# 1541-3mf.net
KiCad netlist of a schematic drawn in EAGLE
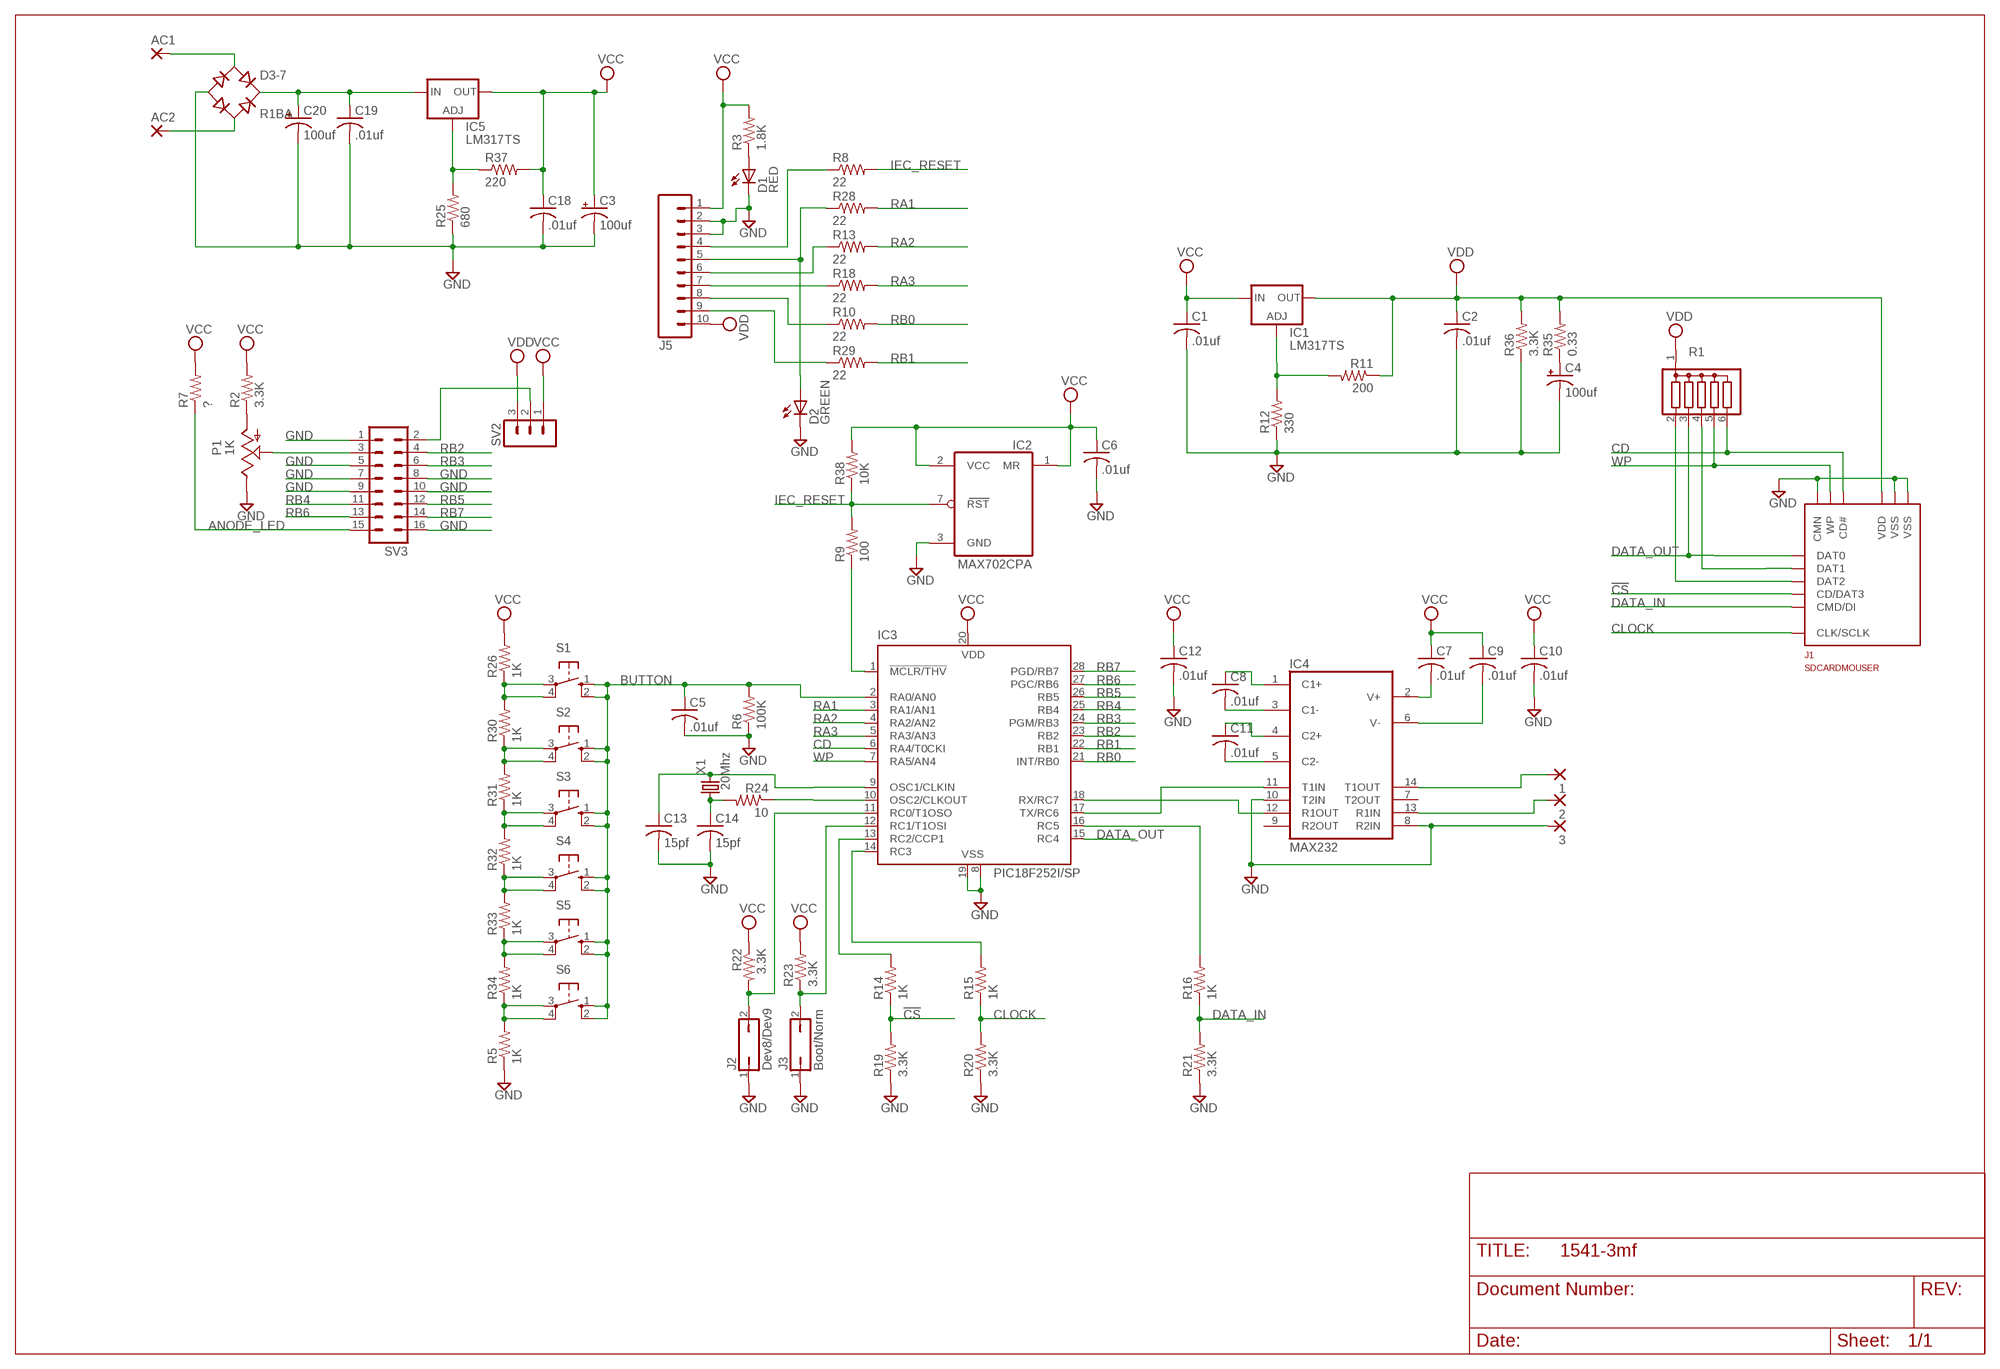
[diagram p0: schematic, sheet 1]

(export (version "E")
  (design (tool "Eeschema 10.0.6"))
  (components
    (comp (ref "1")
      (value "2,15/1,0")
      (footprint "eagle-import:2,15_1,0")
      (libsource (lib "eagle-import") (part "2,15/1,0"))
    )
    (comp (ref "2")
      (value "2,15/1,0")
      (footprint "eagle-import:2,15_1,0")
      (libsource (lib "eagle-import") (part "2,15/1,0"))
    )
    (comp (ref "3")
      (value "2,15/1,0")
      (footprint "eagle-import:2,15_1,0")
      (libsource (lib "eagle-import") (part "2,15/1,0"))
    )
    (comp (ref "AC1")
      (value "2,15/1,0")
      (footprint "eagle-import:2,15_1,0")
      (libsource (lib "eagle-import") (part "2,15/1,0"))
    )
    (comp (ref "AC2")
      (value "2,15/1,0")
      (footprint "eagle-import:2,15_1,0")
      (libsource (lib "eagle-import") (part "2,15/1,0"))
    )
    (comp (ref "C1")
      (value ".01uf")
      (footprint "eagle-import:C025-024X044")
      (libsource (lib "eagle-import") (part "C-US025-024X044"))
    )
    (comp (ref "C2")
      (value ".01uf")
      (footprint "eagle-import:C025-024X044")
      (libsource (lib "eagle-import") (part "C-US025-024X044"))
    )
    (comp (ref "C3")
      (value "100uf")
      (footprint "eagle-import:E2-5")
      (libsource (lib "eagle-import") (part "CPOL-USE2-5"))
    )
    (comp (ref "C4")
      (value "100uf")
      (footprint "eagle-import:E2-5")
      (libsource (lib "eagle-import") (part "CPOL-USE2-5"))
    )
    (comp (ref "C5")
      (value ".01uf")
      (footprint "eagle-import:C025-024X044")
      (libsource (lib "eagle-import") (part "C-US025-024X044"))
    )
    (comp (ref "C6")
      (value ".01uf")
      (footprint "eagle-import:C025-024X044")
      (libsource (lib "eagle-import") (part "C-US025-024X044"))
    )
    (comp (ref "C7")
      (value ".01uf")
      (footprint "eagle-import:C025-024X044")
      (libsource (lib "eagle-import") (part "C-US025-024X044"))
    )
    (comp (ref "C8")
      (value ".01uf")
      (footprint "eagle-import:C025-024X044")
      (libsource (lib "eagle-import") (part "C-US025-024X044"))
    )
    (comp (ref "C9")
      (value ".01uf")
      (footprint "eagle-import:C025-024X044")
      (libsource (lib "eagle-import") (part "C-US025-024X044"))
    )
    (comp (ref "C10")
      (value ".01uf")
      (footprint "eagle-import:C025-024X044")
      (libsource (lib "eagle-import") (part "C-US025-024X044"))
    )
    (comp (ref "C11")
      (value ".01uf")
      (footprint "eagle-import:C025-024X044")
      (libsource (lib "eagle-import") (part "C-US025-024X044"))
    )
    (comp (ref "C12")
      (value ".01uf")
      (footprint "eagle-import:C025-024X044")
      (libsource (lib "eagle-import") (part "C-US025-024X044"))
    )
    (comp (ref "C13")
      (value "15pf")
      (footprint "eagle-import:C025-024X044")
      (libsource (lib "eagle-import") (part "C-US025-024X044"))
    )
    (comp (ref "C14")
      (value "15pf")
      (footprint "eagle-import:C025-024X044")
      (libsource (lib "eagle-import") (part "C-US025-024X044"))
    )
    (comp (ref "C18")
      (value ".01uf")
      (footprint "eagle-import:C025-024X044")
      (libsource (lib "eagle-import") (part "C-US025-024X044"))
    )
    (comp (ref "C19")
      (value ".01uf")
      (footprint "eagle-import:C025-024X044")
      (libsource (lib "eagle-import") (part "C-US025-024X044"))
    )
    (comp (ref "C20")
      (value "100uf")
      (footprint "eagle-import:E2-5")
      (libsource (lib "eagle-import") (part "CPOL-USE2-5"))
    )
    (comp (ref "D1")
      (value "RED")
      (footprint "eagle-import:LED3MM")
      (libsource (lib "eagle-import") (part "LED3MM"))
    )
    (comp (ref "D2")
      (value "GREEN")
      (footprint "eagle-import:LED3MM")
      (libsource (lib "eagle-import") (part "LED3MM"))
    )
    (comp (ref "D3-7")
      (value "R1BA")
      (footprint "eagle-import:RB1A")
      (libsource (lib "eagle-import") (part "RB1A"))
    )
    (comp (ref "IC1")
      (value "LM317TS")
      (footprint "eagle-import:317TS")
      (libsource (lib "eagle-import") (part "LM317TS"))
    )
    (comp (ref "IC2")
      (value "MAX702CPA")
      (footprint "eagle-import:DIL08")
      (fields (field (name "MF") "MAXIM") (field (name "MPN") "MAX702CPA+"))
      (libsource (lib "eagle-import") (part "MAX702CPA"))
    )
    (comp (ref "IC3")
      (value "PIC18F252I/SP")
      (footprint "eagle-import:DIL28-3")
      (fields (field (name "MF") "MICROCHIP") (field (name "MPN") "PIC16F870-I/SP"))
      (libsource (lib "eagle-import") (part "PIC16870PF"))
    )
    (comp (ref "IC4")
      (value "MAX232")
      (footprint "eagle-import:DIL16")
      (fields (field (name "MF") "MAXIM") (field (name "MPN") "MAX232ACPE+"))
      (libsource (lib "eagle-import") (part "MAX232"))
    )
    (comp (ref "IC5")
      (value "LM317TS")
      (footprint "eagle-import:317TS")
      (libsource (lib "eagle-import") (part "LM317TS"))
    )
    (comp (ref "J1")
      (value "SDCARDMOUSER")
      (footprint "eagle-import:SCDA1A")
      (libsource (lib "eagle-import") (part "SDCARDMOUSER"))
    )
    (comp (ref "J2")
      (value "Dev8/Dev9")
      (footprint "eagle-import:JP1")
      (libsource (lib "eagle-import") (part "JP1Q"))
    )
    (comp (ref "J3")
      (value "Boot/Norm")
      (footprint "eagle-import:JP1")
      (libsource (lib "eagle-import") (part "JP1Q"))
    )
    (comp (ref "J5")
      (value "M10")
      (footprint "eagle-import:10P")
      (libsource (lib "eagle-import") (part "M10"))
    )
    (comp (ref "P1")
      (value "1K")
      (footprint "eagle-import:LI10")
      (libsource (lib "eagle-import") (part "TRIM_US-LI10"))
    )
    (comp (ref "R1")
      (value "G05R")
      (footprint "eagle-import:SIL6")
      (libsource (lib "eagle-import") (part "G05R"))
    )
    (comp (ref "R2")
      (value "3.3K")
      (footprint "eagle-import:0207_7")
      (libsource (lib "eagle-import") (part "R-US_0207/7"))
    )
    (comp (ref "R3")
      (value "1.8K")
      (footprint "eagle-import:0207_7")
      (libsource (lib "eagle-import") (part "R-US_0207/7"))
    )
    (comp (ref "R5")
      (value "1K")
      (footprint "eagle-import:0207_7")
      (libsource (lib "eagle-import") (part "R-US_0207/7"))
    )
    (comp (ref "R6")
      (value "100K")
      (footprint "eagle-import:0207_7")
      (libsource (lib "eagle-import") (part "R-US_0207/7"))
    )
    (comp (ref "R7")
      (value "?")
      (footprint "eagle-import:0207_7")
      (libsource (lib "eagle-import") (part "R-US_0207/7"))
    )
    (comp (ref "R8")
      (value "22")
      (footprint "eagle-import:0207_7")
      (libsource (lib "eagle-import") (part "R-US_0207/7"))
    )
    (comp (ref "R9")
      (value "100")
      (footprint "eagle-import:0207_7")
      (libsource (lib "eagle-import") (part "R-US_0207/7"))
    )
    (comp (ref "R10")
      (value "22")
      (footprint "eagle-import:0207_7")
      (libsource (lib "eagle-import") (part "R-US_0207/7"))
    )
    (comp (ref "R11")
      (value "200")
      (footprint "eagle-import:0207_7")
      (libsource (lib "eagle-import") (part "R-US_0207/7"))
    )
    (comp (ref "R12")
      (value "330")
      (footprint "eagle-import:0207_7")
      (libsource (lib "eagle-import") (part "R-US_0207/7"))
    )
    (comp (ref "R13")
      (value "22")
      (footprint "eagle-import:0207_7")
      (libsource (lib "eagle-import") (part "R-US_0207/7"))
    )
    (comp (ref "R14")
      (value "1K")
      (footprint "eagle-import:0207_7")
      (libsource (lib "eagle-import") (part "R-US_0207/7"))
    )
    (comp (ref "R15")
      (value "1K")
      (footprint "eagle-import:0207_7")
      (libsource (lib "eagle-import") (part "R-US_0207/7"))
    )
    (comp (ref "R16")
      (value "1K")
      (footprint "eagle-import:0207_7")
      (libsource (lib "eagle-import") (part "R-US_0207/7"))
    )
    (comp (ref "R18")
      (value "22")
      (footprint "eagle-import:0207_7")
      (libsource (lib "eagle-import") (part "R-US_0207/7"))
    )
    (comp (ref "R19")
      (value "3.3K")
      (footprint "eagle-import:0207_7")
      (libsource (lib "eagle-import") (part "R-US_0207/7"))
    )
    (comp (ref "R20")
      (value "3.3K")
      (footprint "eagle-import:0207_7")
      (libsource (lib "eagle-import") (part "R-US_0207/7"))
    )
    (comp (ref "R21")
      (value "3.3K")
      (footprint "eagle-import:0207_7")
      (libsource (lib "eagle-import") (part "R-US_0207/7"))
    )
    (comp (ref "R22")
      (value "3.3K")
      (footprint "eagle-import:0207_7")
      (libsource (lib "eagle-import") (part "R-US_0207/7"))
    )
    (comp (ref "R23")
      (value "3.3K")
      (footprint "eagle-import:0207_7")
      (libsource (lib "eagle-import") (part "R-US_0207/7"))
    )
    (comp (ref "R24")
      (value "10")
      (footprint "eagle-import:0207_7")
      (libsource (lib "eagle-import") (part "R-US_0207/7"))
    )
    (comp (ref "R25")
      (value "680")
      (footprint "eagle-import:0207_7")
      (libsource (lib "eagle-import") (part "R-US_0207/7"))
    )
    (comp (ref "R26")
      (value "1K")
      (footprint "eagle-import:0207_7")
      (libsource (lib "eagle-import") (part "R-US_0207/7"))
    )
    (comp (ref "R28")
      (value "22")
      (footprint "eagle-import:0207_7")
      (libsource (lib "eagle-import") (part "R-US_0207/7"))
    )
    (comp (ref "R29")
      (value "22")
      (footprint "eagle-import:0207_7")
      (libsource (lib "eagle-import") (part "R-US_0207/7"))
    )
    (comp (ref "R30")
      (value "1K")
      (footprint "eagle-import:0207_7")
      (libsource (lib "eagle-import") (part "R-US_0207/7"))
    )
    (comp (ref "R31")
      (value "1K")
      (footprint "eagle-import:0207_7")
      (libsource (lib "eagle-import") (part "R-US_0207/7"))
    )
    (comp (ref "R32")
      (value "1K")
      (footprint "eagle-import:0207_7")
      (libsource (lib "eagle-import") (part "R-US_0207/7"))
    )
    (comp (ref "R33")
      (value "1K")
      (footprint "eagle-import:0207_7")
      (libsource (lib "eagle-import") (part "R-US_0207/7"))
    )
    (comp (ref "R34")
      (value "1K")
      (footprint "eagle-import:0207_7")
      (libsource (lib "eagle-import") (part "R-US_0207/7"))
    )
    (comp (ref "R35")
      (value "0.33")
      (footprint "eagle-import:0207_7")
      (libsource (lib "eagle-import") (part "R-US_0207/7"))
    )
    (comp (ref "R36")
      (value "3.3K")
      (footprint "eagle-import:0207_7")
      (libsource (lib "eagle-import") (part "R-US_0207/7"))
    )
    (comp (ref "R37")
      (value "220")
      (footprint "eagle-import:0207_7")
      (libsource (lib "eagle-import") (part "R-US_0207/7"))
    )
    (comp (ref "R38")
      (value "10K")
      (footprint "eagle-import:0207_7")
      (libsource (lib "eagle-import") (part "R-US_0207/7"))
    )
    (comp (ref "S1")
      (value "10-XX")
      (footprint "eagle-import:B3F-10XX")
      (fields (field (name "MPN") "B3F-1000"))
      (libsource (lib "eagle-import") (part "10-XX"))
    )
    (comp (ref "S2")
      (value "10-XX")
      (footprint "eagle-import:B3F-10XX")
      (fields (field (name "MPN") "B3F-1000"))
      (libsource (lib "eagle-import") (part "10-XX"))
    )
    (comp (ref "S3")
      (value "10-XX")
      (footprint "eagle-import:B3F-10XX")
      (fields (field (name "MPN") "B3F-1000"))
      (libsource (lib "eagle-import") (part "10-XX"))
    )
    (comp (ref "S4")
      (value "10-XX")
      (footprint "eagle-import:B3F-10XX")
      (fields (field (name "MPN") "B3F-1000"))
      (libsource (lib "eagle-import") (part "10-XX"))
    )
    (comp (ref "S5")
      (value "10-XX")
      (footprint "eagle-import:B3F-10XX")
      (fields (field (name "MPN") "B3F-1000"))
      (libsource (lib "eagle-import") (part "10-XX"))
    )
    (comp (ref "S6")
      (value "10-XX")
      (footprint "eagle-import:B3F-10XX")
      (fields (field (name "MPN") "B3F-1000"))
      (libsource (lib "eagle-import") (part "10-XX"))
    )
    (comp (ref "SV2")
      (value "MA03-1")
      (footprint "eagle-import:MA03-1")
      (libsource (lib "eagle-import") (part "MA03-1"))
    )
    (comp (ref "SV3")
      (value "ML16")
      (footprint "eagle-import:ML16")
      (libsource (lib "eagle-import") (part "ML16"))
    )
    (comp (ref "X1")
      (value "20Mhz")
      (footprint "eagle-import:HC49U70")
      (libsource (lib "eagle-import") (part "CRYSTALHC49U70"))
    )
  )
  (nets
    (net (code "1") (name "/ANODE_LED") (class "Default")
      (node (ref "R7") (pin "1") (pinfunction "1_1") (pintype "passive"))
      (node (ref "SV3") (pin "15") (pinfunction "15_15") (pintype "passive"))
    )
    (net (code "2") (name "/BUTTON") (class "Default")
      (node (ref "C5") (pin "1") (pinfunction "1_1") (pintype "passive"))
      (node (ref "IC3") (pin "2") (pinfunction "RA0/AN0_2") (pintype "bidirectional"))
      (node (ref "R6") (pin "2") (pinfunction "2_2") (pintype "passive"))
      (node (ref "S1") (pin "1") (pinfunction "S_1") (pintype "passive"))
      (node (ref "S1") (pin "2") (pinfunction "S1_2") (pintype "passive"))
      (node (ref "S2") (pin "1") (pinfunction "S_1") (pintype "passive"))
      (node (ref "S2") (pin "2") (pinfunction "S1_2") (pintype "passive"))
      (node (ref "S3") (pin "1") (pinfunction "S_1") (pintype "passive"))
      (node (ref "S3") (pin "2") (pinfunction "S1_2") (pintype "passive"))
      (node (ref "S4") (pin "1") (pinfunction "S_1") (pintype "passive"))
      (node (ref "S4") (pin "2") (pinfunction "S1_2") (pintype "passive"))
      (node (ref "S5") (pin "1") (pinfunction "S_1") (pintype "passive"))
      (node (ref "S5") (pin "2") (pinfunction "S1_2") (pintype "passive"))
      (node (ref "S6") (pin "1") (pinfunction "S_1") (pintype "passive"))
      (node (ref "S6") (pin "2") (pinfunction "S1_2") (pintype "passive"))
    )
    (net (code "3") (name "/CD") (class "Default")
      (node (ref "IC3") (pin "6") (pinfunction "RA4/T0CKI_6") (pintype "bidirectional"))
      (node (ref "J1") (pin "10") (pinfunction "CD#_10") (pintype "output"))
      (node (ref "R1") (pin "6") (pinfunction "6_6") (pintype "passive"))
    )
    (net (code "4") (name "/CLOCK") (class "Default")
      (node (ref "J1") (pin "5") (pinfunction "CLK/SCLK_5") (pintype "bidirectional"))
      (node (ref "R15") (pin "1") (pinfunction "1_1") (pintype "passive"))
      (node (ref "R20") (pin "2") (pinfunction "2_2") (pintype "passive"))
    )
    (net (code "5") (name "/DATA_IN") (class "Default")
      (node (ref "J1") (pin "2") (pinfunction "CMD/DI_2") (pintype "bidirectional"))
      (node (ref "R16") (pin "1") (pinfunction "1_1") (pintype "passive"))
      (node (ref "R21") (pin "2") (pinfunction "2_2") (pintype "passive"))
    )
    (net (code "6") (name "/DATA_OUT") (class "Default")
      (node (ref "IC3") (pin "15") (pinfunction "RC4_15") (pintype "bidirectional"))
      (node (ref "J1") (pin "7") (pinfunction "DAT0_7") (pintype "bidirectional"))
      (node (ref "R1") (pin "3") (pinfunction "3_3") (pintype "passive"))
    )
    (net (code "7") (name "/IEC_RESET") (class "Default")
      (node (ref "IC2") (pin "7") (pinfunction "RST_7") (pintype "output"))
      (node (ref "R38") (pin "1") (pinfunction "1_1") (pintype "passive"))
      (node (ref "R8") (pin "2") (pinfunction "2_2") (pintype "passive"))
      (node (ref "R9") (pin "2") (pinfunction "2_2") (pintype "passive"))
    )
    (net (code "8") (name "/RA1") (class "Default")
      (node (ref "IC3") (pin "3") (pinfunction "RA1/AN1_3") (pintype "bidirectional"))
      (node (ref "R28") (pin "2") (pinfunction "2_2") (pintype "passive"))
    )
    (net (code "9") (name "/RA2") (class "Default")
      (node (ref "IC3") (pin "4") (pinfunction "RA2/AN2_4") (pintype "bidirectional"))
      (node (ref "R13") (pin "2") (pinfunction "2_2") (pintype "passive"))
    )
    (net (code "10") (name "/RA3") (class "Default")
      (node (ref "IC3") (pin "5") (pinfunction "RA3/AN3_5") (pintype "bidirectional"))
      (node (ref "R18") (pin "2") (pinfunction "2_2") (pintype "passive"))
    )
    (net (code "11") (name "/RB0") (class "Default")
      (node (ref "IC3") (pin "21") (pinfunction "INT/RB0_21") (pintype "bidirectional"))
      (node (ref "R10") (pin "2") (pinfunction "2_2") (pintype "passive"))
    )
    (net (code "12") (name "/RB1") (class "Default")
      (node (ref "IC3") (pin "22") (pinfunction "RB1_22") (pintype "bidirectional"))
      (node (ref "R29") (pin "2") (pinfunction "2_2") (pintype "passive"))
    )
    (net (code "13") (name "/RB2") (class "Default")
      (node (ref "IC3") (pin "23") (pinfunction "RB2_23") (pintype "bidirectional"))
      (node (ref "SV3") (pin "4") (pinfunction "4_4") (pintype "passive"))
    )
    (net (code "14") (name "/RB3") (class "Default")
      (node (ref "IC3") (pin "24") (pinfunction "PGM/RB3_24") (pintype "bidirectional"))
      (node (ref "SV3") (pin "6") (pinfunction "6_6") (pintype "passive"))
    )
    (net (code "15") (name "/RB4") (class "Default")
      (node (ref "IC3") (pin "25") (pinfunction "RB4_25") (pintype "bidirectional"))
      (node (ref "SV3") (pin "11") (pinfunction "11_11") (pintype "passive"))
    )
    (net (code "16") (name "/RB5") (class "Default")
      (node (ref "IC3") (pin "26") (pinfunction "RB5_26") (pintype "bidirectional"))
      (node (ref "SV3") (pin "12") (pinfunction "12_12") (pintype "passive"))
    )
    (net (code "17") (name "/RB6") (class "Default")
      (node (ref "IC3") (pin "27") (pinfunction "PGC/RB6_27") (pintype "bidirectional"))
      (node (ref "SV3") (pin "13") (pinfunction "13_13") (pintype "passive"))
    )
    (net (code "18") (name "/RB7") (class "Default")
      (node (ref "IC3") (pin "28") (pinfunction "PGD/RB7_28") (pintype "bidirectional"))
      (node (ref "SV3") (pin "14") (pinfunction "14_14") (pintype "passive"))
    )
    (net (code "19") (name "/WP") (class "Default")
      (node (ref "IC3") (pin "7") (pinfunction "RA5/AN4_7") (pintype "bidirectional"))
      (node (ref "J1") (pin "12") (pinfunction "WP_12") (pintype "output"))
      (node (ref "R1") (pin "5") (pinfunction "5_5") (pintype "passive"))
    )
    (net (code "20") (name "/~{CS}") (class "Default")
      (node (ref "J1") (pin "1") (pinfunction "CD/DAT3_1") (pintype "bidirectional"))
      (node (ref "R14") (pin "1") (pinfunction "1_1") (pintype "passive"))
      (node (ref "R19") (pin "2") (pinfunction "2_2") (pintype "passive"))
    )
    (net (code "21") (name "GND") (class "Default")
      (node (ref "3") (pin "1") (pinfunction "P_1") (pintype "passive"))
      (node (ref "C1") (pin "2") (pinfunction "2_2") (pintype "passive"))
      (node (ref "C10") (pin "2") (pinfunction "2_2") (pintype "passive"))
      (node (ref "C12") (pin "2") (pinfunction "2_2") (pintype "passive"))
      (node (ref "C13") (pin "2") (pinfunction "2_2") (pintype "passive"))
      (node (ref "C14") (pin "2") (pinfunction "2_2") (pintype "passive"))
      (node (ref "C18") (pin "2") (pinfunction "2_2") (pintype "passive"))
      (node (ref "C19") (pin "2") (pinfunction "2_2") (pintype "passive"))
      (node (ref "C2") (pin "2") (pinfunction "2_2") (pintype "passive"))
      (node (ref "C20") (pin "-") (pinfunction "-_-") (pintype "passive"))
      (node (ref "C3") (pin "-") (pinfunction "-_-") (pintype "passive"))
      (node (ref "C4") (pin "-") (pinfunction "-_-") (pintype "passive"))
      (node (ref "C5") (pin "2") (pinfunction "2_2") (pintype "passive"))
      (node (ref "C6") (pin "2") (pinfunction "2_2") (pintype "passive"))
      (node (ref "D1") (pin "K") (pinfunction "C_K") (pintype "passive"))
      (node (ref "D2") (pin "K") (pinfunction "C_K") (pintype "passive"))
      (node (ref "D3-7") (pin "-") (pinfunction "-_-") (pintype "passive"))
      (node (ref "IC2") (pin "3") (pinfunction "GND_3") (pintype "power_in"))
      (node (ref "IC3") (pin "19") (pinfunction "VSS_19") (pintype "power_in"))
      (node (ref "IC3") (pin "8") (pinfunction "VSS_8") (pintype "power_in"))
      (node (ref "IC4") (pin "10") (pinfunction "T2IN_10") (pintype "input"))
      (node (ref "IC4") (pin "8") (pinfunction "R2IN_8") (pintype "input"))
      (node (ref "J1") (pin "11") (pinfunction "CMN_11") (pintype "input"))
      (node (ref "J1") (pin "3") (pinfunction "VSS_3") (pintype "power_in"))
      (node (ref "J1") (pin "6") (pinfunction "VSS_6") (pintype "power_in"))
      (node (ref "J2") (pin "1") (pinfunction "1_1") (pintype "passive"))
      (node (ref "J3") (pin "1") (pinfunction "1_1") (pintype "passive"))
      (node (ref "J5") (pin "2") (pinfunction "2_2") (pintype "passive"))
      (node (ref "J5") (pin "3") (pinfunction "3_3") (pintype "passive"))
      (node (ref "P1") (pin "E") (pinfunction "E_E") (pintype "passive"))
      (node (ref "R12") (pin "1") (pinfunction "1_1") (pintype "passive"))
      (node (ref "R19") (pin "1") (pinfunction "1_1") (pintype "passive"))
      (node (ref "R20") (pin "1") (pinfunction "1_1") (pintype "passive"))
      (node (ref "R21") (pin "1") (pinfunction "1_1") (pintype "passive"))
      (node (ref "R25") (pin "1") (pinfunction "1_1") (pintype "passive"))
      (node (ref "R36") (pin "1") (pinfunction "1_1") (pintype "passive"))
      (node (ref "R5") (pin "1") (pinfunction "1_1") (pintype "passive"))
      (node (ref "R6") (pin "1") (pinfunction "1_1") (pintype "passive"))
      (node (ref "SV3") (pin "1") (pinfunction "1_1") (pintype "passive"))
      (node (ref "SV3") (pin "10") (pinfunction "10_10") (pintype "passive"))
      (node (ref "SV3") (pin "16") (pinfunction "16_16") (pintype "passive"))
      (node (ref "SV3") (pin "5") (pinfunction "5_5") (pintype "passive"))
      (node (ref "SV3") (pin "7") (pinfunction "7_7") (pintype "passive"))
      (node (ref "SV3") (pin "8") (pinfunction "8_8") (pintype "passive"))
      (node (ref "SV3") (pin "9") (pinfunction "9_9") (pintype "passive"))
    )
    (net (code "22") (name "Net-(1-P)") (class "Default")
      (node (ref "1") (pin "1") (pinfunction "P_1") (pintype "passive"))
      (node (ref "IC4") (pin "14") (pinfunction "T1OUT_14") (pintype "output"))
    )
    (net (code "23") (name "Net-(2-P)") (class "Default")
      (node (ref "2") (pin "1") (pinfunction "P_1") (pintype "passive"))
      (node (ref "IC4") (pin "13") (pinfunction "R1IN_13") (pintype "input"))
    )
    (net (code "24") (name "Net-(AC1-P)") (class "Default")
      (node (ref "AC1") (pin "1") (pinfunction "P_1") (pintype "passive"))
      (node (ref "D3-7") (pin "AC1") (pinfunction "AC1_AC1") (pintype "passive"))
    )
    (net (code "25") (name "Net-(AC2-P)") (class "Default")
      (node (ref "AC2") (pin "1") (pinfunction "P_1") (pintype "passive"))
      (node (ref "D3-7") (pin "AC2") (pinfunction "AC2_AC2") (pintype "passive"))
    )
    (net (code "26") (name "Net-(C4-Pad+)") (class "Default")
      (node (ref "C4") (pin "+") (pinfunction "+_+") (pintype "passive"))
      (node (ref "R35") (pin "1") (pinfunction "1_1") (pintype "passive"))
    )
    (net (code "27") (name "Net-(C14-Pad1)") (class "Default")
      (node (ref "C14") (pin "1") (pinfunction "1_1") (pintype "passive"))
      (node (ref "R24") (pin "2") (pinfunction "2_2") (pintype "passive"))
      (node (ref "X1") (pin "1") (pinfunction "1_1") (pintype "passive"))
    )
    (net (code "28") (name "Net-(D1-PadA)") (class "Default")
      (node (ref "D1") (pin "A") (pinfunction "A_A") (pintype "passive"))
      (node (ref "R3") (pin "1") (pinfunction "1_1") (pintype "passive"))
    )
    (net (code "29") (name "Net-(D2-PadA)") (class "Default")
      (node (ref "D2") (pin "A") (pinfunction "A_A") (pintype "passive"))
      (node (ref "J5") (pin "5") (pinfunction "5_5") (pintype "passive"))
      (node (ref "R28") (pin "1") (pinfunction "1_1") (pintype "passive"))
    )
    (net (code "30") (name "Net-(IC1-ADJ)") (class "Default")
      (node (ref "IC1") (pin "1") (pinfunction "ADJ_1") (pintype "input"))
      (node (ref "R11") (pin "2") (pinfunction "2_2") (pintype "passive"))
      (node (ref "R12") (pin "2") (pinfunction "2_2") (pintype "passive"))
    )
    (net (code "31") (name "Net-(IC3-OSC1{slash}CLKIN)") (class "Default")
      (node (ref "C13") (pin "1") (pinfunction "1_1") (pintype "passive"))
      (node (ref "IC3") (pin "9") (pinfunction "OSC1/CLKIN_9") (pintype "input"))
      (node (ref "X1") (pin "2") (pinfunction "2_2") (pintype "passive"))
    )
    (net (code "32") (name "Net-(IC3-OSC2{slash}CLKOUT)") (class "Default")
      (node (ref "IC3") (pin "10") (pinfunction "OSC2/CLKOUT_10") (pintype "output"))
      (node (ref "R24") (pin "1") (pinfunction "1_1") (pintype "passive"))
    )
    (net (code "33") (name "Net-(IC3-RC0{slash}T1OSO)") (class "Default")
      (node (ref "IC3") (pin "11") (pinfunction "RC0/T1OSO_11") (pintype "bidirectional"))
      (node (ref "J2") (pin "2") (pinfunction "2_2") (pintype "passive"))
      (node (ref "R22") (pin "2") (pinfunction "2_2") (pintype "passive"))
    )
    (net (code "34") (name "Net-(IC3-RC1{slash}T1OSI)") (class "Default")
      (node (ref "IC3") (pin "12") (pinfunction "RC1/T1OSI_12") (pintype "bidirectional"))
      (node (ref "J3") (pin "2") (pinfunction "2_2") (pintype "passive"))
      (node (ref "R23") (pin "1") (pinfunction "1_1") (pintype "passive"))
    )
    (net (code "35") (name "Net-(IC3-RC2{slash}CCP1)") (class "Default")
      (node (ref "IC3") (pin "13") (pinfunction "RC2/CCP1_13") (pintype "bidirectional"))
      (node (ref "R14") (pin "2") (pinfunction "2_2") (pintype "passive"))
    )
    (net (code "36") (name "Net-(IC3-RC3)") (class "Default")
      (node (ref "IC3") (pin "14") (pinfunction "RC3_14") (pintype "bidirectional"))
      (node (ref "R15") (pin "2") (pinfunction "2_2") (pintype "passive"))
    )
    (net (code "37") (name "Net-(IC3-RC5)") (class "Default")
      (node (ref "IC3") (pin "16") (pinfunction "RC5_16") (pintype "bidirectional"))
      (node (ref "R16") (pin "2") (pinfunction "2_2") (pintype "passive"))
    )
    (net (code "38") (name "Net-(IC3-RX{slash}RC7)") (class "Default")
      (node (ref "IC3") (pin "18") (pinfunction "RX/RC7_18") (pintype "bidirectional"))
      (node (ref "IC4") (pin "12") (pinfunction "R1OUT_12") (pintype "output"))
    )
    (net (code "39") (name "Net-(IC3-TX{slash}RC6)") (class "Default")
      (node (ref "IC3") (pin "17") (pinfunction "TX/RC6_17") (pintype "bidirectional"))
      (node (ref "IC4") (pin "11") (pinfunction "T1IN_11") (pintype "input"))
    )
    (net (code "40") (name "Net-(IC3-~{MCLR{slash}THV})") (class "Default")
      (node (ref "IC3") (pin "1") (pinfunction "~{MCLR/THV}_1") (pintype "input"))
      (node (ref "R9") (pin "1") (pinfunction "1_1") (pintype "passive"))
    )
    (net (code "41") (name "Net-(IC4A-C1+)") (class "Default")
      (node (ref "C8") (pin "1") (pinfunction "1_1") (pintype "passive"))
      (node (ref "IC4") (pin "1") (pinfunction "C1+_1") (pintype "bidirectional"))
    )
    (net (code "42") (name "Net-(IC4A-C1-)") (class "Default")
      (node (ref "C8") (pin "2") (pinfunction "2_2") (pintype "passive"))
      (node (ref "IC4") (pin "3") (pinfunction "C1-_3") (pintype "bidirectional"))
    )
    (net (code "43") (name "Net-(IC4A-C2+)") (class "Default")
      (node (ref "C11") (pin "1") (pinfunction "1_1") (pintype "passive"))
      (node (ref "IC4") (pin "4") (pinfunction "C2+_4") (pintype "bidirectional"))
    )
    (net (code "44") (name "Net-(IC4A-C2-)") (class "Default")
      (node (ref "C11") (pin "2") (pinfunction "2_2") (pintype "passive"))
      (node (ref "IC4") (pin "5") (pinfunction "C2-_5") (pintype "bidirectional"))
    )
    (net (code "45") (name "Net-(IC4A-V+)") (class "Default")
      (node (ref "C7") (pin "2") (pinfunction "2_2") (pintype "passive"))
      (node (ref "IC4") (pin "2") (pinfunction "V+_2") (pintype "bidirectional"))
    )
    (net (code "46") (name "Net-(IC4A-V-)") (class "Default")
      (node (ref "C9") (pin "2") (pinfunction "2_2") (pintype "passive"))
      (node (ref "IC4") (pin "6") (pinfunction "V-_6") (pintype "bidirectional"))
    )
    (net (code "47") (name "Net-(IC5-ADJ)") (class "Default")
      (node (ref "IC5") (pin "1") (pinfunction "ADJ_1") (pintype "input"))
      (node (ref "R25") (pin "2") (pinfunction "2_2") (pintype "passive"))
      (node (ref "R37") (pin "1") (pinfunction "1_1") (pintype "passive"))
    )
    (net (code "48") (name "Net-(IC5-IN)") (class "Default")
      (node (ref "C19") (pin "1") (pinfunction "1_1") (pintype "passive"))
      (node (ref "C20") (pin "+") (pinfunction "+_+") (pintype "passive"))
      (node (ref "D3-7") (pin "+") (pinfunction "+_+") (pintype "passive"))
      (node (ref "IC5") (pin "3") (pinfunction "IN_3") (pintype "input"))
    )
    (net (code "49") (name "Net-(J1A-DAT1)") (class "Default")
      (node (ref "J1") (pin "8") (pinfunction "DAT1_8") (pintype "bidirectional"))
      (node (ref "R1") (pin "4") (pinfunction "4_4") (pintype "passive"))
    )
    (net (code "50") (name "Net-(J1A-DAT2)") (class "Default")
      (node (ref "J1") (pin "9") (pinfunction "DAT2_9") (pintype "bidirectional"))
      (node (ref "R1") (pin "2") (pinfunction "2_2") (pintype "passive"))
    )
    (net (code "51") (name "Net-(J5-Pad4)") (class "Default")
      (node (ref "J5") (pin "4") (pinfunction "4_4") (pintype "passive"))
      (node (ref "R8") (pin "1") (pinfunction "1_1") (pintype "passive"))
    )
    (net (code "52") (name "Net-(J5-Pad6)") (class "Default")
      (node (ref "J5") (pin "6") (pinfunction "6_6") (pintype "passive"))
      (node (ref "R13") (pin "1") (pinfunction "1_1") (pintype "passive"))
    )
    (net (code "53") (name "Net-(J5-Pad7)") (class "Default")
      (node (ref "J5") (pin "7") (pinfunction "7_7") (pintype "passive"))
      (node (ref "R18") (pin "1") (pinfunction "1_1") (pintype "passive"))
    )
    (net (code "54") (name "Net-(J5-Pad8)") (class "Default")
      (node (ref "J5") (pin "8") (pinfunction "8_8") (pintype "passive"))
      (node (ref "R10") (pin "1") (pinfunction "1_1") (pintype "passive"))
    )
    (net (code "55") (name "Net-(J5-Pad9)") (class "Default")
      (node (ref "J5") (pin "9") (pinfunction "9_9") (pintype "passive"))
      (node (ref "R29") (pin "1") (pinfunction "1_1") (pintype "passive"))
    )
    (net (code "56") (name "Net-(P1-PadA)") (class "Default")
      (node (ref "P1") (pin "A") (pinfunction "A_A") (pintype "passive"))
      (node (ref "R2") (pin "1") (pinfunction "1_1") (pintype "passive"))
    )
    (net (code "57") (name "Net-(P1-PadS)") (class "Default")
      (node (ref "P1") (pin "S") (pinfunction "S_S") (pintype "passive"))
      (node (ref "SV3") (pin "3") (pinfunction "3_3") (pintype "passive"))
    )
    (net (code "58") (name "Net-(S1-P)") (class "Default")
      (node (ref "R26") (pin "1") (pinfunction "1_1") (pintype "passive"))
      (node (ref "R30") (pin "2") (pinfunction "2_2") (pintype "passive"))
      (node (ref "S1") (pin "3") (pinfunction "P_3") (pintype "passive"))
      (node (ref "S1") (pin "4") (pinfunction "P1_4") (pintype "passive"))
    )
    (net (code "59") (name "Net-(S2-P)") (class "Default")
      (node (ref "R30") (pin "1") (pinfunction "1_1") (pintype "passive"))
      (node (ref "R31") (pin "2") (pinfunction "2_2") (pintype "passive"))
      (node (ref "S2") (pin "3") (pinfunction "P_3") (pintype "passive"))
      (node (ref "S2") (pin "4") (pinfunction "P1_4") (pintype "passive"))
    )
    (net (code "60") (name "Net-(S3-P)") (class "Default")
      (node (ref "R31") (pin "1") (pinfunction "1_1") (pintype "passive"))
      (node (ref "R32") (pin "2") (pinfunction "2_2") (pintype "passive"))
      (node (ref "S3") (pin "3") (pinfunction "P_3") (pintype "passive"))
      (node (ref "S3") (pin "4") (pinfunction "P1_4") (pintype "passive"))
    )
    (net (code "61") (name "Net-(S4-P)") (class "Default")
      (node (ref "R32") (pin "1") (pinfunction "1_1") (pintype "passive"))
      (node (ref "R33") (pin "2") (pinfunction "2_2") (pintype "passive"))
      (node (ref "S4") (pin "3") (pinfunction "P_3") (pintype "passive"))
      (node (ref "S4") (pin "4") (pinfunction "P1_4") (pintype "passive"))
    )
    (net (code "62") (name "Net-(S5-P)") (class "Default")
      (node (ref "R33") (pin "1") (pinfunction "1_1") (pintype "passive"))
      (node (ref "R34") (pin "2") (pinfunction "2_2") (pintype "passive"))
      (node (ref "S5") (pin "3") (pinfunction "P_3") (pintype "passive"))
      (node (ref "S5") (pin "4") (pinfunction "P1_4") (pintype "passive"))
    )
    (net (code "63") (name "Net-(S6-P)") (class "Default")
      (node (ref "R34") (pin "1") (pinfunction "1_1") (pintype "passive"))
      (node (ref "R5") (pin "2") (pinfunction "2_2") (pintype "passive"))
      (node (ref "S6") (pin "3") (pinfunction "P_3") (pintype "passive"))
      (node (ref "S6") (pin "4") (pinfunction "P1_4") (pintype "passive"))
    )
    (net (code "64") (name "Net-(SV2-Pad2)") (class "Default")
      (node (ref "SV2") (pin "2") (pinfunction "2_2") (pintype "passive"))
      (node (ref "SV3") (pin "2") (pinfunction "2_2") (pintype "passive"))
    )
    (net (code "65") (name "VCC") (class "Default")
      (node (ref "C1") (pin "1") (pinfunction "1_1") (pintype "passive"))
      (node (ref "C10") (pin "1") (pinfunction "1_1") (pintype "passive"))
      (node (ref "C12") (pin "1") (pinfunction "1_1") (pintype "passive"))
      (node (ref "C18") (pin "1") (pinfunction "1_1") (pintype "passive"))
      (node (ref "C3") (pin "+") (pinfunction "+_+") (pintype "passive"))
      (node (ref "C6") (pin "1") (pinfunction "1_1") (pintype "passive"))
      (node (ref "C7") (pin "1") (pinfunction "1_1") (pintype "passive"))
      (node (ref "C9") (pin "1") (pinfunction "1_1") (pintype "passive"))
      (node (ref "IC1") (pin "3") (pinfunction "IN_3") (pintype "input"))
      (node (ref "IC2") (pin "1") (pinfunction "MR_1") (pintype "input"))
      (node (ref "IC2") (pin "2") (pinfunction "VCC_2") (pintype "power_in"))
      (node (ref "IC3") (pin "20") (pinfunction "VDD_20") (pintype "power_in"))
      (node (ref "IC5") (pin "2") (pinfunction "OUT_2") (pintype "passive"))
      (node (ref "J5") (pin "1") (pinfunction "1_1") (pintype "passive"))
      (node (ref "R2") (pin "2") (pinfunction "2_2") (pintype "passive"))
      (node (ref "R22") (pin "1") (pinfunction "1_1") (pintype "passive"))
      (node (ref "R23") (pin "2") (pinfunction "2_2") (pintype "passive"))
      (node (ref "R26") (pin "2") (pinfunction "2_2") (pintype "passive"))
      (node (ref "R3") (pin "2") (pinfunction "2_2") (pintype "passive"))
      (node (ref "R37") (pin "2") (pinfunction "2_2") (pintype "passive"))
      (node (ref "R38") (pin "2") (pinfunction "2_2") (pintype "passive"))
      (node (ref "R7") (pin "2") (pinfunction "2_2") (pintype "passive"))
      (node (ref "SV2") (pin "1") (pinfunction "1_1") (pintype "passive"))
    )
    (net (code "66") (name "VDD") (class "Default")
      (node (ref "C2") (pin "1") (pinfunction "1_1") (pintype "passive"))
      (node (ref "IC1") (pin "2") (pinfunction "OUT_2") (pintype "passive"))
      (node (ref "J1") (pin "4") (pinfunction "VDD_4") (pintype "power_in"))
      (node (ref "J5") (pin "10") (pinfunction "10_10") (pintype "passive"))
      (node (ref "R1") (pin "1") (pinfunction "1_1") (pintype "passive"))
      (node (ref "R11") (pin "1") (pinfunction "1_1") (pintype "passive"))
      (node (ref "R35") (pin "2") (pinfunction "2_2") (pintype "passive"))
      (node (ref "R36") (pin "2") (pinfunction "2_2") (pintype "passive"))
      (node (ref "SV2") (pin "3") (pinfunction "3_3") (pintype "passive"))
    )
    (net (code "67") (name "unconnected-(IC4A-R2OUT-Pad9)") (class "Default")
      (node (ref "IC4") (pin "9") (pinfunction "R2OUT_9") (pintype "output"))
    )
    (net (code "68") (name "unconnected-(IC4A-T2OUT-Pad7)") (class "Default")
      (node (ref "IC4") (pin "7") (pinfunction "T2OUT_7") (pintype "output"))
    )
  )
)
